# Ethernet.net
KiCad netlist of a schematic drawn in Altium Designer
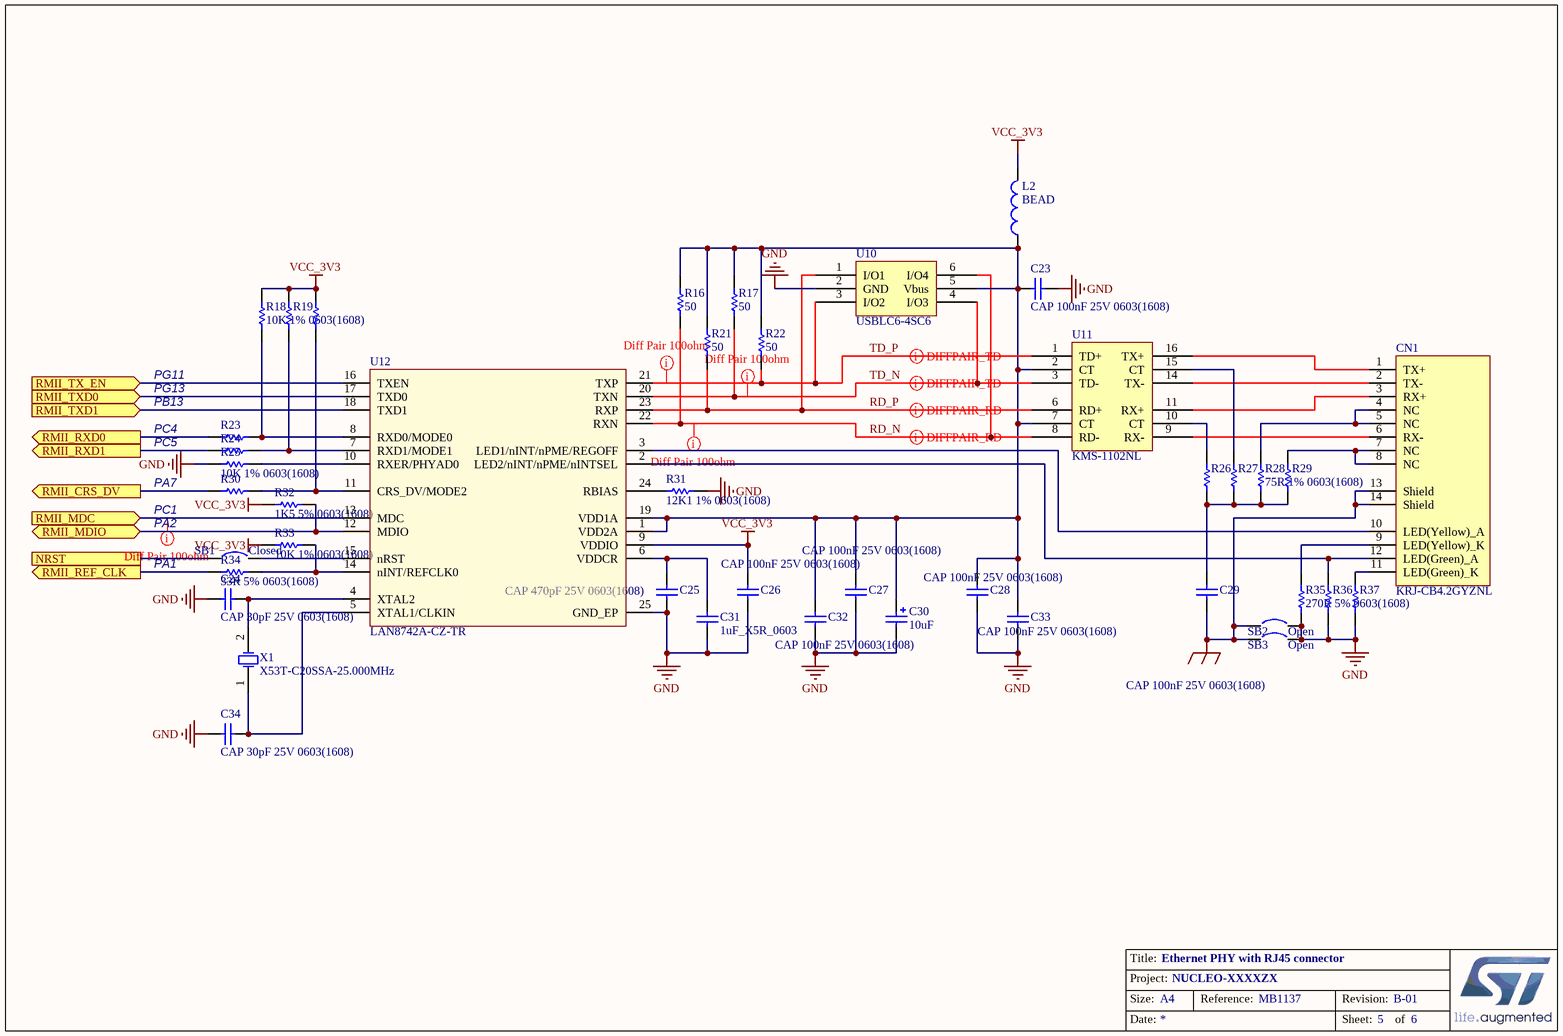
[diagram p0: Ethernet.SchDoc]

(export (version "E")
  (design (tool "Eeschema 10.0.6"))
  (components
    (comp (ref "C23")
      (value "CAP 100nF 25V 0603(1608)")
      (footprint "CAPC0603(1608)100_N")
      (description "CAP 100nF 25V ±5% 0603 (1608 Metric) Thickness 1mm SMD")
      (fields (field (name "TOLERANCE") "Â±5%"))
      (libsource (lib "Altium Content Vault") (part "CAP"))
    )
    (comp (ref "C24")
      (value "CAP 30pF 25V 0603(1608)")
      (footprint "CAPC0603(1608)100_N")
      (description "CAP 30pF 25V ±5% 0603 (1608 Metric) Thickness 1mm SMD")
      (fields (field (name "TOLERANCE") "Â±5%"))
      (libsource (lib "Altium Content Vault") (part "CAP"))
    )
    (comp (ref "C25")
      (value "CAP 470pF 25V 0603(1608)")
      (footprint "CAPC0603(1608)100_M")
      (description "CAP 470pF 25V ±5% 0603 (1608 Metric) Thickness 1mm SMD")
      (fields (field (name "TOLERANCE") "Â±5%"))
      (libsource (lib "Altium Content Vault") (part "CAP"))
    )
    (comp (ref "C26")
      (value "CAP 100nF 25V 0603(1608)")
      (footprint "CAPC0603(1608)100_N")
      (description "CAP 100nF 25V ±5% 0603 (1608 Metric) Thickness 1mm SMD")
      (fields (field (name "TOLERANCE") "Â±5%"))
      (libsource (lib "Altium Content Vault") (part "CAP"))
    )
    (comp (ref "C27")
      (value "CAP 100nF 25V 0603(1608)")
      (footprint "CAPC0603(1608)100_N")
      (description "CAP 100nF 25V ±5% 0603 (1608 Metric) Thickness 1mm SMD")
      (fields (field (name "TOLERANCE") "Â±5%"))
      (libsource (lib "Altium Content Vault") (part "CAP"))
    )
    (comp (ref "C28")
      (value "CAP 100nF 25V 0603(1608)")
      (footprint "CAPC0603(1608)100_N")
      (description "CAP 100nF 25V ±5% 0603 (1608 Metric) Thickness 1mm SMD")
      (fields (field (name "TOLERANCE") "Â±5%"))
      (libsource (lib "Altium Content Vault") (part "CAP"))
    )
    (comp (ref "C29")
      (value "CAP 100nF 25V 0603(1608)")
      (footprint "CAPC0603(1608)100_N")
      (description "CAP 100nF 25V ±5% 0603 (1608 Metric) Thickness 1mm SMD")
      (fields (field (name "TOLERANCE") "Â±5%"))
      (libsource (lib "Altium Content Vault") (part "CAP"))
    )
    (comp (ref "C30")
      (value "10uF")
      (footprint "TAN-A")
      (description "Polarized Capacitor,10uF,10V,10%,typeA,VISHAY")
      (libsource (lib "MCD_TOOLS") (part "Cap_10uF_POL_10%_TANA"))
    )
    (comp (ref "C31")
      (value "1uF_X5R_0603")
      (footprint "0603C")
      (description "0603  X5R 1µF")
      (fields (field (name "TOLERANCE") "10%"))
      (libsource (lib "MB963_1") (part "CAP SMD 0603  X5R 1µF 25V 10%"))
    )
    (comp (ref "C32")
      (value "CAP 100nF 25V 0603(1608)")
      (footprint "CAPC0603(1608)100_N")
      (description "CAP 100nF 25V ±5% 0603 (1608 Metric) Thickness 1mm SMD")
      (fields (field (name "TOLERANCE") "Â±5%"))
      (libsource (lib "Altium Content Vault") (part "CAP"))
    )
    (comp (ref "C33")
      (value "CAP 100nF 25V 0603(1608)")
      (footprint "CAPC0603(1608)100_N")
      (description "CAP 100nF 25V ±5% 0603 (1608 Metric) Thickness 1mm SMD")
      (fields (field (name "TOLERANCE") "Â±5%"))
      (libsource (lib "Altium Content Vault") (part "CAP"))
    )
    (comp (ref "C34")
      (value "CAP 30pF 25V 0603(1608)")
      (footprint "CAPC0603(1608)100_N")
      (description "CAP 30pF 25V ±5% 0603 (1608 Metric) Thickness 1mm SMD")
      (fields (field (name "TOLERANCE") "Â±5%"))
      (libsource (lib "Altium Content Vault") (part "CAP"))
    )
    (comp (ref "CN1")
      (value "KRJ-CB4.2GYZNL")
      (footprint "RJ45_KRJ-CB4.2GYZNL")
      (description "100 Base-TX (Fast Ethernet) SMD RJ45 single port (1x1) with LEDS Integrated Magnetics Connector")
      (libsource (lib "TAUV_Components") (part "KRJ-CB4.2GYZNL"))
    )
    (comp (ref "L2")
      (value "BEAD")
      (footprint "0603L")
      (description "Inductor")
      (fields (field (name "PUBLISHER") "Altium Limited"))
      (libsource (lib "Miscellaneous Devices") (part "Inductor"))
    )
    (comp (ref "R16")
      (value "50")
      (footprint "0603R")
      (description "Resistor,50,0603,1%,YAGEO")
      (libsource (lib "TAUV_Components") (part "Res_50_1%_0603"))
    )
    (comp (ref "R17")
      (value "50")
      (footprint "0603R")
      (description "Resistor,50,0603,1%,YAGEO")
      (libsource (lib "TAUV_Components") (part "Res_50_1%_0603"))
    )
    (comp (ref "R18")
      (value "10K 1% 0603(1608)")
      (footprint "RESC0603(1608)_N")
      (description "10K 0.1W 1% 0603 (1608 Metric)  SMD")
      (fields (field (name "POWER") "0.1 W") (field (name "TOLERANCE") "1 %"))
      (libsource (lib "Altium Content Vault") (part "RES"))
    )
    (comp (ref "R19")
      (value "10K 1% 0603(1608)")
      (footprint "RESC0603(1608)_N")
      (description "10K 0.1W 1% 0603 (1608 Metric)  SMD")
      (fields (field (name "POWER") "0.1 W") (field (name "TOLERANCE") "1 %"))
      (libsource (lib "Altium Content Vault") (part "RES"))
    )
    (comp (ref "R20")
      (value "10K 1% 0603(1608)")
      (footprint "RESC0603(1608)_N")
      (description "10K 0.1W 1% 0603 (1608 Metric)  SMD")
      (fields (field (name "POWER") "0.1 W") (field (name "TOLERANCE") "1 %"))
      (libsource (lib "Altium Content Vault") (part "RES"))
    )
    (comp (ref "R21")
      (value "50")
      (footprint "0603R")
      (description "Resistor,50,0603,1%,YAGEO")
      (libsource (lib "TAUV_Components") (part "Res_50_1%_0603"))
    )
    (comp (ref "R22")
      (value "50")
      (footprint "0603R")
      (description "Resistor,50,0603,1%,YAGEO")
      (libsource (lib "TAUV_Components") (part "Res_50_1%_0603"))
    )
    (comp (ref "R23")
      (value "33R 5% 0603(1608)")
      (footprint "RESC0603(1608)_M")
      (description "33R 0.1W 5% 0603 (1608 Metric)  SMD")
      (fields (field (name "TOLERANCE") "5 %") (field (name "POWER") "0.1 W"))
      (libsource (lib "Altium Content Vault") (part "RES"))
    )
    (comp (ref "R24")
      (value "33R 5% 0603(1608)")
      (footprint "RESC0603(1608)_M")
      (description "33R 0.1W 5% 0603 (1608 Metric)  SMD")
      (fields (field (name "TOLERANCE") "5 %") (field (name "POWER") "0.1 W"))
      (libsource (lib "Altium Content Vault") (part "RES"))
    )
    (comp (ref "R25")
      (value "10K 1% 0603(1608)")
      (footprint "RESC0603(1608)_N")
      (description "10K 0.1W 1% 0603 (1608 Metric)  SMD")
      (fields (field (name "POWER") "0.1 W") (field (name "TOLERANCE") "1 %"))
      (libsource (lib "Altium Content Vault") (part "RES"))
    )
    (comp (ref "R26")
      (value "75R 1% 0603(1608)")
      (footprint "RESC0603(1608)_M")
      (description "75R 0.1W 1% 0603 (1608 Metric)  SMD")
      (fields (field (name "POWER") "0.1 W") (field (name "TOLERANCE") "1 %"))
      (libsource (lib "Altium Content Vault") (part "RES"))
    )
    (comp (ref "R27")
      (value "75R 1% 0603(1608)")
      (footprint "RESC0603(1608)_M")
      (description "75R 0.1W 1% 0603 (1608 Metric)  SMD")
      (fields (field (name "POWER") "0.1 W") (field (name "TOLERANCE") "1 %"))
      (libsource (lib "Altium Content Vault") (part "RES"))
    )
    (comp (ref "R28")
      (value "75R 1% 0603(1608)")
      (footprint "RESC0603(1608)_M")
      (description "75R 0.1W 1% 0603 (1608 Metric)  SMD")
      (fields (field (name "POWER") "0.1 W") (field (name "TOLERANCE") "1 %"))
      (libsource (lib "Altium Content Vault") (part "RES"))
    )
    (comp (ref "R29")
      (value "75R 1% 0603(1608)")
      (footprint "RESC0603(1608)_M")
      (description "75R 0.1W 1% 0603 (1608 Metric)  SMD")
      (fields (field (name "POWER") "0.1 W") (field (name "TOLERANCE") "1 %"))
      (libsource (lib "Altium Content Vault") (part "RES"))
    )
    (comp (ref "R30")
      (value "33R 5% 0603(1608)")
      (footprint "RESC0603(1608)_M")
      (description "33R 0.1W 5% 0603 (1608 Metric)  SMD")
      (fields (field (name "TOLERANCE") "5 %") (field (name "POWER") "0.1 W"))
      (libsource (lib "Altium Content Vault") (part "RES"))
    )
    (comp (ref "R31")
      (value "12K1 1% 0603(1608)")
      (footprint "RESC0603(1608)_M")
      (description "12K1 0.1W 1% 0603 (1608 Metric)  SMD")
      (fields (field (name "POWER") "0.1 W") (field (name "TOLERANCE") "1 %"))
      (libsource (lib "Altium Content Vault") (part "RES"))
    )
    (comp (ref "R32")
      (value "1K5 5% 0603(1608)")
      (footprint "RESC0603(1608)_M")
      (description "1K5 0.1W 5% 0603 (1608 Metric)  SMD")
      (fields (field (name "POWER") "0.1 W") (field (name "TOLERANCE") "5 %"))
      (libsource (lib "Altium Content Vault") (part "RES"))
    )
    (comp (ref "R33")
      (value "10K 1% 0603(1608)")
      (footprint "RESC0603(1608)_N")
      (description "10K 0.1W 1% 0603 (1608 Metric)  SMD")
      (fields (field (name "POWER") "0.1 W") (field (name "TOLERANCE") "1 %"))
      (libsource (lib "Altium Content Vault") (part "RES"))
    )
    (comp (ref "R34")
      (value "33R 5% 0603(1608)")
      (footprint "RESC0603(1608)_M")
      (description "33R 0.1W 5% 0603 (1608 Metric)  SMD")
      (fields (field (name "TOLERANCE") "5 %") (field (name "POWER") "0.1 W"))
      (libsource (lib "Altium Content Vault") (part "RES"))
    )
    (comp (ref "R35")
      (value "270R 5% 0603(1608)")
      (footprint "RESC0603(1608)_N")
      (description "270R 0.1W 5% 0603 (1608 Metric)  SMD")
      (fields (field (name "POWER") "0.1 W") (field (name "TOLERANCE") "5 %"))
      (libsource (lib "Altium Content Vault") (part "RES"))
    )
    (comp (ref "R36")
      (value "270R 5% 0603(1608)")
      (footprint "RESC0603(1608)_N")
      (description "270R 0.1W 5% 0603 (1608 Metric)  SMD")
      (fields (field (name "POWER") "0.1 W") (field (name "TOLERANCE") "5 %"))
      (libsource (lib "Altium Content Vault") (part "RES"))
    )
    (comp (ref "R37")
      (value "270R 5% 0603(1608)")
      (footprint "RESC0603(1608)_N")
      (description "270R 0.1W 5% 0603 (1608 Metric)  SMD")
      (fields (field (name "POWER") "0.1 W") (field (name "TOLERANCE") "5 %"))
      (libsource (lib "Altium Content Vault") (part "RES"))
    )
    (comp (ref "SB1")
      (value "Closed")
      (footprint "SB_0603")
      (description "Circuit Breaker")
      (fields (field (name "PUBLISHER") "Altium Limited"))
      (libsource (lib "MB1167") (part "Circuit Breaker_close"))
    )
    (comp (ref "SB2")
      (value "Open")
      (footprint "SB_0603")
      (description "Circuit Breaker")
      (fields (field (name "PUBLISHER") "Altium Limited"))
      (libsource (lib "MB1167") (part "Circuit Breaker"))
    )
    (comp (ref "SB3")
      (value "Open")
      (footprint "SB_0603")
      (description "Circuit Breaker")
      (fields (field (name "PUBLISHER") "Altium Limited"))
      (libsource (lib "MB1167") (part "Circuit Breaker"))
    )
    (comp (ref "U10")
      (value "USBLC6-4SC6")
      (footprint "SOT23-6L")
      (libsource (lib "TAUV_Components") (part "USBLC6-4SC6"))
    )
    (comp (ref "U11")
      (value "KMS-1102NL")
      (footprint "Transformer")
      (libsource (lib "TAUV_Components") (part "KMS-1102NL"))
    )
    (comp (ref "U12")
      (value "LAN8742A-CZ-TR")
      (footprint "QFN24_0R5_4X4")
      (libsource (lib "TAUV_Components") (part "LAN8742A-CZ-TR"))
    )
    (comp (ref "X1")
      (value "X53T-C20SSA-25.000MHz")
      (footprint "XTAL_2SM_5R0X3R2")
      (description "Crystal Oscillator")
      (fields (field (name "PUBLISHER") "Altium Limited"))
      (libsource (lib "TAUV_Components") (part "XTAL_5032"))
    )
  )
  (nets
    (net (code "1") (name "/NRST") (class "Default")
      (node (ref "SB1") (pin "1") (pinfunction "1_1") (pintype "passive"))
    )
    (net (code "2") (name "/RD_N") (class "Default")
      (node (ref "R16") (pin "1") (pinfunction "1_1") (pintype "passive"))
      (node (ref "U10") (pin "6") (pinfunction "I/O4_6") (pintype "passive"))
      (node (ref "U11") (pin "8") (pinfunction "RD-_8") (pintype "passive"))
      (node (ref "U12") (pin "22") (pinfunction "RXN_22") (pintype "passive"))
    )
    (net (code "3") (name "/RD_P") (class "Default")
      (node (ref "R21") (pin "1") (pinfunction "1_1") (pintype "passive"))
      (node (ref "U10") (pin "1") (pinfunction "I/O1_1") (pintype "passive"))
      (node (ref "U11") (pin "6") (pinfunction "RD+_6") (pintype "passive"))
      (node (ref "U12") (pin "23") (pinfunction "RXP_23") (pintype "passive"))
    )
    (net (code "4") (name "/RMII_CRS_DV") (class "Default")
      (node (ref "R30") (pin "1") (pinfunction "1_1") (pintype "passive"))
    )
    (net (code "5") (name "/RMII_MDC") (class "Default")
      (node (ref "U12") (pin "13") (pinfunction "MDC_13") (pintype "passive"))
    )
    (net (code "6") (name "/RMII_MDIO") (class "Default")
      (node (ref "R32") (pin "2") (pinfunction "2_2") (pintype "passive"))
      (node (ref "U12") (pin "12") (pinfunction "MDIO_12") (pintype "passive"))
    )
    (net (code "7") (name "/RMII_REF_CLK") (class "Default")
      (node (ref "R34") (pin "1") (pinfunction "1_1") (pintype "passive"))
    )
    (net (code "8") (name "/RMII_RXD0") (class "Default")
      (node (ref "R23") (pin "1") (pinfunction "1_1") (pintype "passive"))
    )
    (net (code "9") (name "/RMII_RXD1") (class "Default")
      (node (ref "R24") (pin "1") (pinfunction "1_1") (pintype "passive"))
    )
    (net (code "10") (name "/RMII_TXD0") (class "Default")
      (node (ref "U12") (pin "17") (pinfunction "TXD0_17") (pintype "passive"))
    )
    (net (code "11") (name "/RMII_TXD1") (class "Default")
      (node (ref "U12") (pin "18") (pinfunction "TXD1_18") (pintype "passive"))
    )
    (net (code "12") (name "/RMII_TX_EN") (class "Default")
      (node (ref "U12") (pin "16") (pinfunction "TXEN_16") (pintype "passive"))
    )
    (net (code "13") (name "/TD_N") (class "Default")
      (node (ref "R17") (pin "1") (pinfunction "1_1") (pintype "passive"))
      (node (ref "U10") (pin "4") (pinfunction "I/O3_4") (pintype "passive"))
      (node (ref "U11") (pin "3") (pinfunction "TD-_3") (pintype "passive"))
      (node (ref "U12") (pin "20") (pinfunction "TXN_20") (pintype "passive"))
    )
    (net (code "14") (name "/TD_P") (class "Default")
      (node (ref "R22") (pin "1") (pinfunction "1_1") (pintype "passive"))
      (node (ref "U10") (pin "3") (pinfunction "I/O2_3") (pintype "passive"))
      (node (ref "U11") (pin "1") (pinfunction "TD+_1") (pintype "passive"))
      (node (ref "U12") (pin "21") (pinfunction "TXP_21") (pintype "passive"))
    )
    (net (code "15") (name "EGND") (class "Default")
      (node (ref "C29") (pin "1") (pinfunction "1_1") (pintype "passive"))
      (node (ref "CN1") (pin "13") (pinfunction "Shield_13") (pintype "passive"))
      (node (ref "CN1") (pin "14") (pinfunction "Shield_14") (pintype "passive"))
      (node (ref "SB2") (pin "1") (pinfunction "1_1") (pintype "passive"))
      (node (ref "SB3") (pin "1") (pinfunction "1_1") (pintype "passive"))
    )
    (net (code "16") (name "GND") (class "Default")
      (node (ref "C23") (pin "2") (pinfunction "2_2") (pintype "passive"))
      (node (ref "C24") (pin "1") (pinfunction "1_1") (pintype "passive"))
      (node (ref "C25") (pin "1") (pinfunction "1_1") (pintype "passive"))
      (node (ref "C26") (pin "1") (pinfunction "1_1") (pintype "passive"))
      (node (ref "C27") (pin "1") (pinfunction "1_1") (pintype "passive"))
      (node (ref "C28") (pin "1") (pinfunction "1_1") (pintype "passive"))
      (node (ref "C30") (pin "2") (pinfunction "2_2") (pintype "passive"))
      (node (ref "C31") (pin "2") (pinfunction "2_2") (pintype "passive"))
      (node (ref "C32") (pin "1") (pinfunction "1_1") (pintype "passive"))
      (node (ref "C33") (pin "1") (pinfunction "1_1") (pintype "passive"))
      (node (ref "C34") (pin "1") (pinfunction "1_1") (pintype "passive"))
      (node (ref "R25") (pin "1") (pinfunction "1_1") (pintype "passive"))
      (node (ref "R31") (pin "2") (pinfunction "2_2") (pintype "passive"))
      (node (ref "R35") (pin "1") (pinfunction "1_1") (pintype "passive"))
      (node (ref "R36") (pin "1") (pinfunction "1_1") (pintype "passive"))
      (node (ref "R37") (pin "1") (pinfunction "1_1") (pintype "passive"))
      (node (ref "SB2") (pin "2") (pinfunction "2_2") (pintype "passive"))
      (node (ref "SB3") (pin "2") (pinfunction "2_2") (pintype "passive"))
      (node (ref "U10") (pin "2") (pinfunction "GND_2") (pintype "passive"))
      (node (ref "U12") (pin "25") (pinfunction "GND_EP_25") (pintype "passive"))
    )
    (net (code "17") (name "Net-(C29-Pad2)") (class "Default")
      (node (ref "C29") (pin "2") (pinfunction "2_2") (pintype "passive"))
      (node (ref "R26") (pin "1") (pinfunction "1_1") (pintype "passive"))
      (node (ref "R27") (pin "1") (pinfunction "1_1") (pintype "passive"))
      (node (ref "R28") (pin "1") (pinfunction "1_1") (pintype "passive"))
      (node (ref "R29") (pin "1") (pinfunction "1_1") (pintype "passive"))
    )
    (net (code "18") (name "Net-(CN1-LED(Green)_A)") (class "Default")
      (node (ref "CN1") (pin "12") (pinfunction "LED(Green)_A_12") (pintype "passive"))
      (node (ref "R36") (pin "2") (pinfunction "2_2") (pintype "passive"))
      (node (ref "U12") (pin "2") (pinfunction "LED2/nINT/nPME/nINTSEL_2") (pintype "passive"))
    )
    (net (code "19") (name "Net-(CN1-LED(Green)_K)") (class "Default")
      (node (ref "CN1") (pin "11") (pinfunction "LED(Green)_K_11") (pintype "passive"))
      (node (ref "R37") (pin "2") (pinfunction "2_2") (pintype "passive"))
    )
    (net (code "20") (name "Net-(CN1-LED(Yellow)_A)") (class "Default")
      (node (ref "CN1") (pin "10") (pinfunction "LED(Yellow)_A_10") (pintype "passive"))
      (node (ref "U12") (pin "3") (pinfunction "LED1/nINT/nPME/REGOFF_3") (pintype "passive"))
    )
    (net (code "21") (name "Net-(CN1-LED(Yellow)_K)") (class "Default")
      (node (ref "CN1") (pin "9") (pinfunction "LED(Yellow)_K_9") (pintype "passive"))
      (node (ref "R35") (pin "2") (pinfunction "2_2") (pintype "passive"))
    )
    (net (code "22") (name "Net-(CN1-NC-Pad4)") (class "Default")
      (node (ref "CN1") (pin "4") (pinfunction "NC_4") (pintype "passive"))
      (node (ref "CN1") (pin "5") (pinfunction "NC_5") (pintype "passive"))
      (node (ref "R28") (pin "2") (pinfunction "2_2") (pintype "passive"))
    )
    (net (code "23") (name "Net-(CN1-NC-Pad7)") (class "Default")
      (node (ref "CN1") (pin "7") (pinfunction "NC_7") (pintype "passive"))
      (node (ref "CN1") (pin "8") (pinfunction "NC_8") (pintype "passive"))
      (node (ref "R29") (pin "2") (pinfunction "2_2") (pintype "passive"))
    )
    (net (code "24") (name "Net-(CN1-RX+)") (class "Default")
      (node (ref "CN1") (pin "3") (pinfunction "RX+_3") (pintype "passive"))
      (node (ref "U11") (pin "11") (pinfunction "RX+_11") (pintype "passive"))
    )
    (net (code "25") (name "Net-(CN1-RX-)") (class "Default")
      (node (ref "CN1") (pin "6") (pinfunction "RX-_6") (pintype "passive"))
      (node (ref "U11") (pin "9") (pinfunction "RX-_9") (pintype "passive"))
    )
    (net (code "26") (name "Net-(CN1-TX+)") (class "Default")
      (node (ref "CN1") (pin "1") (pinfunction "TX+_1") (pintype "passive"))
      (node (ref "U11") (pin "16") (pinfunction "TX+_16") (pintype "passive"))
    )
    (net (code "27") (name "Net-(CN1-TX-)") (class "Default")
      (node (ref "CN1") (pin "2") (pinfunction "TX-_2") (pintype "passive"))
      (node (ref "U11") (pin "14") (pinfunction "TX-_14") (pintype "passive"))
    )
    (net (code "28") (name "Net-(R26-Pad2)") (class "Default")
      (node (ref "R26") (pin "2") (pinfunction "2_2") (pintype "passive"))
      (node (ref "U11") (pin "10") (pinfunction "CT_10") (pintype "passive"))
    )
    (net (code "29") (name "Net-(R27-Pad2)") (class "Default")
      (node (ref "R27") (pin "2") (pinfunction "2_2") (pintype "passive"))
      (node (ref "U11") (pin "15") (pinfunction "CT_15") (pintype "passive"))
    )
    (net (code "30") (name "Net-(U10-Vbus)") (class "Default")
      (node (ref "C23") (pin "1") (pinfunction "1_1") (pintype "passive"))
      (node (ref "C27") (pin "2") (pinfunction "2_2") (pintype "passive"))
      (node (ref "C28") (pin "2") (pinfunction "2_2") (pintype "passive"))
      (node (ref "C30") (pin "1") (pinfunction "1_1") (pintype "passive"))
      (node (ref "C32") (pin "2") (pinfunction "2_2") (pintype "passive"))
      (node (ref "C33") (pin "2") (pinfunction "2_2") (pintype "passive"))
      (node (ref "L2") (pin "1") (pinfunction "1_1") (pintype "passive"))
      (node (ref "R16") (pin "2") (pinfunction "2_2") (pintype "passive"))
      (node (ref "R17") (pin "2") (pinfunction "2_2") (pintype "passive"))
      (node (ref "R21") (pin "2") (pinfunction "2_2") (pintype "passive"))
      (node (ref "R22") (pin "2") (pinfunction "2_2") (pintype "passive"))
      (node (ref "U10") (pin "5") (pinfunction "Vbus_5") (pintype "passive"))
      (node (ref "U11") (pin "2") (pinfunction "CT_2") (pintype "passive"))
      (node (ref "U11") (pin "7") (pinfunction "CT_7") (pintype "passive"))
      (node (ref "U12") (pin "1") (pinfunction "VDD2A_1") (pintype "passive"))
      (node (ref "U12") (pin "19") (pinfunction "VDD1A_19") (pintype "passive"))
    )
    (net (code "31") (name "Net-(U12-CRS_DV{slash}MODE2)") (class "Default")
      (node (ref "R20") (pin "1") (pinfunction "1_1") (pintype "passive"))
      (node (ref "R30") (pin "2") (pinfunction "2_2") (pintype "passive"))
      (node (ref "U12") (pin "11") (pinfunction "CRS_DV/MODE2_11") (pintype "passive"))
    )
    (net (code "32") (name "Net-(U12-RBIAS)") (class "Default")
      (node (ref "R31") (pin "1") (pinfunction "1_1") (pintype "passive"))
      (node (ref "U12") (pin "24") (pinfunction "RBIAS_24") (pintype "passive"))
    )
    (net (code "33") (name "Net-(U12-RXD0{slash}MODE0)") (class "Default")
      (node (ref "R18") (pin "1") (pinfunction "1_1") (pintype "passive"))
      (node (ref "R23") (pin "2") (pinfunction "2_2") (pintype "passive"))
      (node (ref "U12") (pin "8") (pinfunction "RXD0/MODE0_8") (pintype "passive"))
    )
    (net (code "34") (name "Net-(U12-RXD1{slash}MODE1)") (class "Default")
      (node (ref "R19") (pin "1") (pinfunction "1_1") (pintype "passive"))
      (node (ref "R24") (pin "2") (pinfunction "2_2") (pintype "passive"))
      (node (ref "U12") (pin "7") (pinfunction "RXD1/MODE1_7") (pintype "passive"))
    )
    (net (code "35") (name "Net-(U12-RXER{slash}PHYAD0)") (class "Default")
      (node (ref "R25") (pin "2") (pinfunction "2_2") (pintype "passive"))
      (node (ref "U12") (pin "10") (pinfunction "RXER/PHYAD0_10") (pintype "passive"))
    )
    (net (code "36") (name "Net-(U12-VDDCR)") (class "Default")
      (node (ref "C25") (pin "2") (pinfunction "2_2") (pintype "passive"))
      (node (ref "C31") (pin "1") (pinfunction "1_1") (pintype "passive"))
      (node (ref "U12") (pin "6") (pinfunction "VDDCR_6") (pintype "passive"))
    )
    (net (code "37") (name "Net-(U12-XTAL1{slash}CLKIN)") (class "Default")
      (node (ref "C34") (pin "2") (pinfunction "2_2") (pintype "passive"))
      (node (ref "U12") (pin "5") (pinfunction "XTAL1/CLKIN_5") (pintype "passive"))
      (node (ref "X1") (pin "1") (pinfunction "OSC1_1") (pintype "passive"))
    )
    (net (code "38") (name "Net-(U12-XTAL2)") (class "Default")
      (node (ref "C24") (pin "2") (pinfunction "2_2") (pintype "passive"))
      (node (ref "U12") (pin "4") (pinfunction "XTAL2_4") (pintype "passive"))
      (node (ref "X1") (pin "2") (pinfunction "OSC2_2") (pintype "passive"))
    )
    (net (code "39") (name "Net-(U12-nINT{slash}REFCLK0)") (class "Default")
      (node (ref "R33") (pin "2") (pinfunction "2_2") (pintype "passive"))
      (node (ref "R34") (pin "2") (pinfunction "2_2") (pintype "passive"))
      (node (ref "U12") (pin "14") (pinfunction "nINT/REFCLK0_14") (pintype "passive"))
    )
    (net (code "40") (name "Net-(U12-nRST)") (class "Default")
      (node (ref "SB1") (pin "2") (pinfunction "2_2") (pintype "passive"))
      (node (ref "U12") (pin "15") (pinfunction "nRST_15") (pintype "passive"))
    )
    (net (code "41") (name "VCC_3V3") (class "Default")
      (node (ref "C26") (pin "2") (pinfunction "2_2") (pintype "passive"))
      (node (ref "L2") (pin "2") (pinfunction "2_2") (pintype "passive"))
      (node (ref "R18") (pin "2") (pinfunction "2_2") (pintype "passive"))
      (node (ref "R19") (pin "2") (pinfunction "2_2") (pintype "passive"))
      (node (ref "R20") (pin "2") (pinfunction "2_2") (pintype "passive"))
      (node (ref "R32") (pin "1") (pinfunction "1_1") (pintype "passive"))
      (node (ref "R33") (pin "1") (pinfunction "1_1") (pintype "passive"))
      (node (ref "U12") (pin "9") (pinfunction "VDDIO_9") (pintype "passive"))
    )
  )
)
